# Schematic.net
KiCad netlist of a schematic drawn in Altium Designer
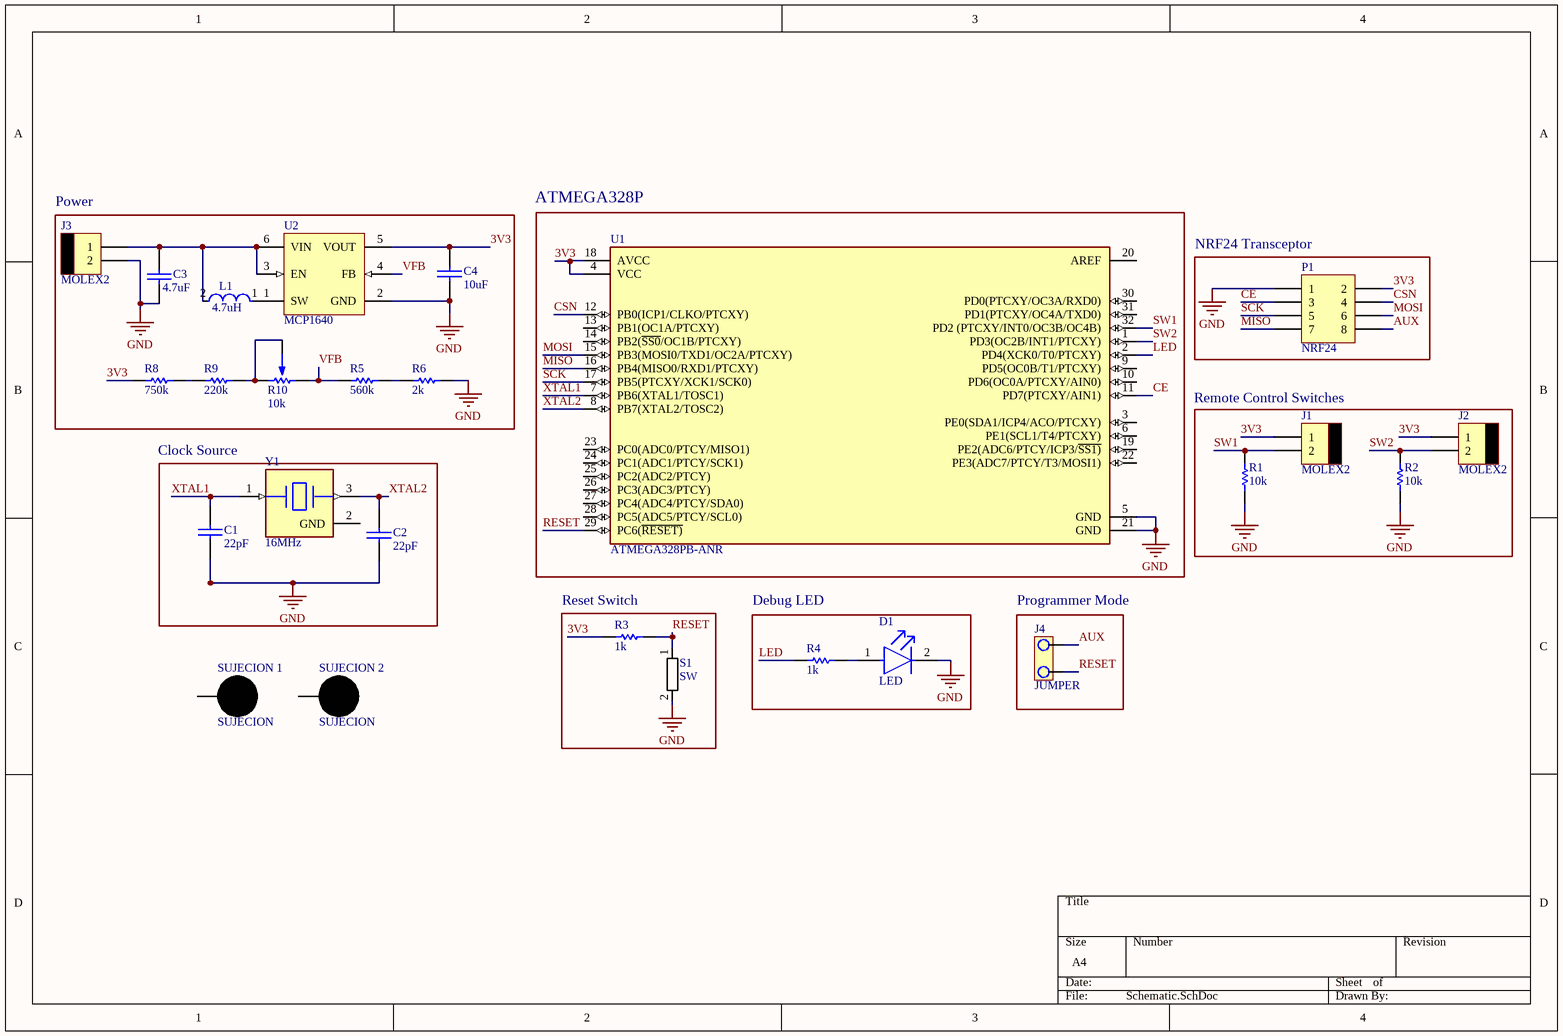
[diagram p0: Schematic.SchDoc]

(export (version "E")
  (design (tool "Eeschema 10.0.6"))
  (components
    (comp (ref "C1") (value "22pF") (footprint "0805") (libsource (lib "LIB PIO IX") (part "CAP")))
    (comp (ref "C2") (value "22pF") (footprint "0805") (libsource (lib "LIB PIO IX") (part "CAP")))
    (comp (ref "C3") (value "4.7uF") (footprint "0805") (libsource (lib "LIB PIO IX") (part "CAP")))
    (comp (ref "C4") (value "10uF") (footprint "0805") (libsource (lib "LIB PIO IX") (part "CAP")))
    (comp (ref "D1")
      (value "LED")
      (footprint "FP-AP1608SGC-MFG")
      (description "Standard LEDs - SMD GREEN WATER CLEAR")
      (libsource (lib "Altium Content Vault") (part "ab1c01a81903e929fc6c44469aada92"))
    )
    (comp (ref "J1") (value "MOLEX2") (footprint "MOLEX2") (libsource (lib "LIB PIO IX") (part "MOLEX2")))
    (comp (ref "J2") (value "MOLEX2") (footprint "MOLEX2") (libsource (lib "LIB PIO IX") (part "MOLEX2")))
    (comp (ref "J3") (value "MOLEX2") (footprint "MOLEX2") (libsource (lib "") (part "MOLEX2_1")))
    (comp (ref "J4") (value "JUMPER") (footprint "JUMPER2") (libsource (lib "LIB PIO IX") (part "JUMPER")))
    (comp (ref "L1")
      (value "4.7uH")
      (footprint "FP-CB2518-IPC_B")
      (description "SMD Inductors 4.7uH ±20% 1.2A 0.13Ω 1007")
      (fields (field (name "TOLERANCE") "20%"))
      (libsource (lib "Altium Content Vault") (part "725321dda6339637d4d059423bc1c3c"))
    )
    (comp (ref "P1")
      (value "NRF24")
      (footprint "HDR2X4")
      (description "Header, 4-Pin, Dual row")
      (fields (field (name "PUBLISHER") "Altium Limited"))
      (libsource (lib "Miscellaneous Connectors") (part "Header 4X2"))
    )
    (comp (ref "R1") (value "10k") (footprint "0805") (libsource (lib "LIB PIO IX") (part "RES")))
    (comp (ref "R2") (value "10k") (footprint "0805") (libsource (lib "LIB PIO IX") (part "RES")))
    (comp (ref "R3") (value "1k") (footprint "0805") (libsource (lib "LIB PIO IX") (part "RES")))
    (comp (ref "R4") (value "1k") (footprint "0805") (libsource (lib "LIB PIO IX") (part "RES")))
    (comp (ref "R5") (value "560k") (footprint "0805") (libsource (lib "LIB PIO IX") (part "RES")))
    (comp (ref "R6") (value "2k") (footprint "0805") (libsource (lib "LIB PIO IX") (part "RES")))
    (comp (ref "R8") (value "750k") (footprint "0805") (libsource (lib "LIB PIO IX") (part "RES")))
    (comp (ref "R9") (value "220k") (footprint "0805") (libsource (lib "LIB PIO IX") (part "RES")))
    (comp (ref "R10") (value "10k") (footprint "PRESET V") (libsource (lib "LIB PIO IX") (part "PRESET")))
    (comp (ref "S1")
      (value "SW")
      (footprint "PCBComponent_1")
      (description "Nano Reset SMD Switch")
      (libsource (lib "SMD_SW") (part "Nano RST SW"))
    )
    (comp (ref "SUJECION 1")
      (value "SUJECION")
      (footprint "SUJECION (5.00MM - 3.50MM)")
      (libsource (lib "LIB2013") (part "SUJECION"))
    )
    (comp (ref "SUJECION 2")
      (value "SUJECION")
      (footprint "SUJECION (5.00MM - 3.50MM)")
      (libsource (lib "LIB2013") (part "SUJECION"))
    )
    (comp (ref "U1")
      (value "ATMEGA328PB-ANR")
      (footprint "FP-C04-074-MFG")
      (description "IC MCU 8BIT 32KB FLASH 32TQFP")
      (libsource (lib "Altium Content Vault") (part "ea72676ab472b9c3d110a3743980b8d"))
    )
    (comp (ref "U2")
      (value "MCP1640")
      (footprint "MCHP-SOT-23-CHY6_M")
      (fields (field (name "MANUFACTURER") "Microchip") (field (name "PARTNUMBER") "MCP1640CT-I/CHY"))
      (libsource (lib "Altium Content Vault") (part "MCHP-MCP16XX-SOT-23-6"))
    )
    (comp (ref "Y1")
      (value "16MHz")
      (footprint "FP-CSTNE16M0V530000R0-MFG")
      (description "CERAMIC RES 16.0000MHZ 15PF SMD")
      (fields
        (field (name "TOLERANCE") "0.5%")
        (field (name "MANUFACTURER PART NUMBER") "CSTNE16M0V530000R0")
      )
      (libsource (lib "Altium Content Vault") (part "f88508b02107a2c8e6f46217c19d2b8"))
    )
  )
  (nets
    (net (code "1") (name "/3V3") (class "Default")
      (node (ref "C4") (pin "1") (pinfunction "1_1") (pintype "passive"))
      (node (ref "J1") (pin "1") (pinfunction "1_1") (pintype "passive"))
      (node (ref "J2") (pin "1") (pinfunction "1_1") (pintype "passive"))
      (node (ref "P1") (pin "2") (pinfunction "2_2") (pintype "passive"))
      (node (ref "R3") (pin "1") (pinfunction "1_1") (pintype "passive"))
      (node (ref "R8") (pin "1") (pinfunction "1_1") (pintype "passive"))
      (node (ref "U1") (pin "18") (pinfunction "AVCC_18") (pintype "power_in"))
      (node (ref "U1") (pin "4") (pinfunction "VCC_4") (pintype "power_in"))
      (node (ref "U2") (pin "5") (pinfunction "VOUT_5") (pintype "power_in"))
    )
    (net (code "2") (name "/AUX") (class "Default")
      (node (ref "J4") (pin "1") (pinfunction "1_1") (pintype "passive"))
      (node (ref "P1") (pin "8") (pinfunction "8_8") (pintype "passive"))
    )
    (net (code "3") (name "/CE") (class "Default")
      (node (ref "P1") (pin "3") (pinfunction "3_3") (pintype "passive"))
      (node (ref "U1") (pin "11") (pinfunction "PD7(PTCXY/AIN1)_11") (pintype "bidirectional"))
    )
    (net (code "4") (name "/CSN") (class "Default")
      (node (ref "P1") (pin "4") (pinfunction "4_4") (pintype "passive"))
      (node (ref "U1") (pin "12") (pinfunction "PB0(ICP1/CLKO/PTCXY)_12") (pintype "bidirectional"))
    )
    (net (code "5") (name "/LED") (class "Default")
      (node (ref "R4") (pin "1") (pinfunction "1_1") (pintype "passive"))
      (node (ref "U1") (pin "2") (pinfunction "PD4(XCK0/T0/PTCXY)_2") (pintype "bidirectional"))
    )
    (net (code "6") (name "/MISO") (class "Default")
      (node (ref "P1") (pin "7") (pinfunction "7_7") (pintype "passive"))
      (node (ref "U1") (pin "16") (pinfunction "PB4(MISO0/RXD1/PTCXY)_16") (pintype "bidirectional"))
    )
    (net (code "7") (name "/MOSI") (class "Default")
      (node (ref "P1") (pin "6") (pinfunction "6_6") (pintype "passive"))
      (node (ref "U1") (pin "15") (pinfunction "PB3(MOSI0/TXD1/OC2A/PTCXY)_15") (pintype "bidirectional"))
    )
    (net (code "8") (name "/RESET") (class "Default")
      (node (ref "J4") (pin "2") (pinfunction "2_2") (pintype "passive"))
      (node (ref "R3") (pin "2") (pinfunction "2_2") (pintype "passive"))
      (node (ref "S1") (pin "1") (pintype "passive"))
      (node (ref "U1") (pin "29") (pinfunction "PC6(~{RESET)}_29") (pintype "bidirectional"))
    )
    (net (code "9") (name "/SCK") (class "Default")
      (node (ref "P1") (pin "5") (pinfunction "5_5") (pintype "passive"))
      (node (ref "U1") (pin "17") (pinfunction "PB5(PTCXY/XCK1/SCK0)_17") (pintype "bidirectional"))
    )
    (net (code "10") (name "/SW1") (class "Default")
      (node (ref "J1") (pin "2") (pinfunction "2_2") (pintype "passive"))
      (node (ref "R1") (pin "2") (pinfunction "2_2") (pintype "passive"))
      (node (ref "U1") (pin "32") (pinfunction "PD2_(PTCXY/INT0/OC3B/OC4B)_32") (pintype "bidirectional"))
    )
    (net (code "11") (name "/SW2") (class "Default")
      (node (ref "J2") (pin "2") (pinfunction "2_2") (pintype "passive"))
      (node (ref "R2") (pin "2") (pinfunction "2_2") (pintype "passive"))
      (node (ref "U1") (pin "1") (pinfunction "PD3(OC2B/INT1/PTCXY)_1") (pintype "bidirectional"))
    )
    (net (code "12") (name "/VFB") (class "Default")
      (node (ref "R10") (pin "3") (pinfunction "3_3") (pintype "passive"))
      (node (ref "R5") (pin "1") (pinfunction "1_1") (pintype "passive"))
      (node (ref "U2") (pin "4") (pinfunction "FB_4") (pintype "input"))
    )
    (net (code "13") (name "/XTAL1") (class "Default")
      (node (ref "C1") (pin "1") (pinfunction "1_1") (pintype "passive"))
      (node (ref "U1") (pin "7") (pinfunction "PB6(XTAL1/TOSC1)_7") (pintype "bidirectional"))
      (node (ref "Y1") (pin "1") (pinfunction "Input_1") (pintype "input"))
    )
    (net (code "14") (name "/XTAL2") (class "Default")
      (node (ref "C2") (pin "1") (pinfunction "1_1") (pintype "passive"))
      (node (ref "U1") (pin "8") (pinfunction "PB7(XTAL2/TOSC2)_8") (pintype "bidirectional"))
      (node (ref "Y1") (pin "3") (pinfunction "Output_3") (pintype "output"))
    )
    (net (code "15") (name "GND") (class "Default")
      (node (ref "C1") (pin "2") (pinfunction "2_2") (pintype "passive"))
      (node (ref "C2") (pin "2") (pinfunction "2_2") (pintype "passive"))
      (node (ref "C3") (pin "2") (pinfunction "2_2") (pintype "passive"))
      (node (ref "C4") (pin "2") (pinfunction "2_2") (pintype "passive"))
      (node (ref "D1") (pin "2") (pinfunction "C_2") (pintype "passive"))
      (node (ref "J3") (pin "2") (pinfunction "2_2") (pintype "passive"))
      (node (ref "P1") (pin "1") (pinfunction "1_1") (pintype "passive"))
      (node (ref "R1") (pin "1") (pinfunction "1_1") (pintype "passive"))
      (node (ref "R2") (pin "1") (pinfunction "1_1") (pintype "passive"))
      (node (ref "R6") (pin "2") (pinfunction "2_2") (pintype "passive"))
      (node (ref "S1") (pin "2") (pintype "passive"))
      (node (ref "U1") (pin "21") (pinfunction "GND_21") (pintype "power_in"))
      (node (ref "U1") (pin "5") (pinfunction "GND_5") (pintype "power_in"))
      (node (ref "U2") (pin "2") (pinfunction "GND_2") (pintype "power_in"))
    )
    (net (code "16") (name "Net-(D1-A)") (class "Default")
      (node (ref "D1") (pin "1") (pinfunction "A_1") (pintype "passive"))
      (node (ref "R4") (pin "2") (pinfunction "2_2") (pintype "passive"))
    )
    (net (code "17") (name "Net-(R5-Pad2)") (class "Default")
      (node (ref "R5") (pin "2") (pinfunction "2_2") (pintype "passive"))
      (node (ref "R6") (pin "1") (pinfunction "1_1") (pintype "passive"))
    )
    (net (code "18") (name "Net-(R8-Pad2)") (class "Default")
      (node (ref "R8") (pin "2") (pinfunction "2_2") (pintype "passive"))
      (node (ref "R9") (pin "1") (pinfunction "1_1") (pintype "passive"))
    )
    (net (code "19") (name "Net-(R10-Pad1)") (class "Default")
      (node (ref "R10") (pin "1") (pinfunction "1_1") (pintype "passive"))
      (node (ref "R10") (pin "2") (pinfunction "2_2") (pintype "passive"))
      (node (ref "R9") (pin "2") (pinfunction "2_2") (pintype "passive"))
    )
    (net (code "20") (name "Net-(U2-EN)") (class "Default")
      (node (ref "C3") (pin "1") (pinfunction "1_1") (pintype "passive"))
      (node (ref "J3") (pin "1") (pinfunction "1_1") (pintype "passive"))
      (node (ref "L1") (pin "2") (pinfunction "2_2") (pintype "passive"))
      (node (ref "U2") (pin "3") (pinfunction "EN_3") (pintype "input"))
      (node (ref "U2") (pin "6") (pinfunction "VIN_6") (pintype "power_in"))
    )
    (net (code "21") (name "Net-(U2-SW)") (class "Default")
      (node (ref "L1") (pin "1") (pinfunction "1_1") (pintype "passive"))
      (node (ref "U2") (pin "1") (pinfunction "SW_1") (pintype "power_in"))
    )
    (net (code "22") (name "unconnected-(SUJECION 1-Pad1)") (class "Default")
      (node (ref "SUJECION 1") (pin "1") (pinfunction "1_1") (pintype "passive"))
    )
    (net (code "23") (name "unconnected-(SUJECION 2-Pad1)") (class "Default")
      (node (ref "SUJECION 2") (pin "1") (pinfunction "1_1") (pintype "passive"))
    )
    (net (code "24") (name "unconnected-(U1-AREF-Pad20)") (class "Default")
      (node (ref "U1") (pin "20") (pinfunction "AREF_20") (pintype "passive"))
    )
    (net (code "25") (name "unconnected-(U1-PB1(OC1A{slash}PTCXY)-Pad13)") (class "Default")
      (node (ref "U1") (pin "13") (pinfunction "PB1(OC1A/PTCXY)_13") (pintype "bidirectional"))
    )
    (net (code "26") (name "unconnected-(U1-PB2(~{SS0}{slash}OC1B{slash}PTCXY)-Pad14)") (class "Default")
      (node (ref "U1") (pin "14") (pinfunction "PB2(~{SS0}/OC1B/PTCXY)_14") (pintype "bidirectional"))
    )
    (net (code "27") (name "unconnected-(U1-PC0(ADC0{slash}PTCY{slash}MISO1)-Pad23)") (class "Default")
      (node (ref "U1") (pin "23") (pinfunction "PC0(ADC0/PTCY/MISO1)_23") (pintype "bidirectional"))
    )
    (net (code "28") (name "unconnected-(U1-PC1(ADC1{slash}PTCY{slash}SCK1)-Pad24)") (class "Default")
      (node (ref "U1") (pin "24") (pinfunction "PC1(ADC1/PTCY/SCK1)_24") (pintype "bidirectional"))
    )
    (net (code "29") (name "unconnected-(U1-PC2(ADC2{slash}PTCY)-Pad25)") (class "Default")
      (node (ref "U1") (pin "25") (pinfunction "PC2(ADC2/PTCY)_25") (pintype "bidirectional"))
    )
    (net (code "30") (name "unconnected-(U1-PC3(ADC3{slash}PTCY)-Pad26)") (class "Default")
      (node (ref "U1") (pin "26") (pinfunction "PC3(ADC3/PTCY)_26") (pintype "bidirectional"))
    )
    (net (code "31") (name "unconnected-(U1-PC4(ADC4{slash}PTCY{slash}SDA0)-Pad27)") (class "Default")
      (node (ref "U1") (pin "27") (pinfunction "PC4(ADC4/PTCY/SDA0)_27") (pintype "bidirectional"))
    )
    (net (code "32") (name "unconnected-(U1-PC5(ADC5{slash}PTCY{slash}SCL0)-Pad28)") (class "Default")
      (node (ref "U1") (pin "28") (pinfunction "PC5(ADC5/PTCY/SCL0)_28") (pintype "bidirectional"))
    )
    (net (code "33") (name "unconnected-(U1-PD0(PTCXY{slash}OC3A{slash}RXD0)-Pad30)") (class "Default")
      (node (ref "U1") (pin "30") (pinfunction "PD0(PTCXY/OC3A/RXD0)_30") (pintype "bidirectional"))
    )
    (net (code "34") (name "unconnected-(U1-PD1(PTCXY{slash}OC4A{slash}TXD0)-Pad31)") (class "Default")
      (node (ref "U1") (pin "31") (pinfunction "PD1(PTCXY/OC4A/TXD0)_31") (pintype "bidirectional"))
    )
    (net (code "35") (name "unconnected-(U1-PD5(OC0B{slash}T1{slash}PTCXY)-Pad9)") (class "Default")
      (node (ref "U1") (pin "9") (pinfunction "PD5(OC0B/T1/PTCXY)_9") (pintype "bidirectional"))
    )
    (net (code "36") (name "unconnected-(U1-PD6(OC0A{slash}PTCXY{slash}AIN0)-Pad10)") (class "Default")
      (node (ref "U1") (pin "10") (pinfunction "PD6(OC0A/PTCXY/AIN0)_10") (pintype "bidirectional"))
    )
    (net (code "37") (name "unconnected-(U1-PE0(SDA1{slash}ICP4{slash}ACO{slash}PTCXY)-Pad3)") (class "Default")
      (node (ref "U1") (pin "3") (pinfunction "PE0(SDA1/ICP4/ACO/PTCXY)_3") (pintype "bidirectional"))
    )
    (net (code "38") (name "unconnected-(U1-PE1(SCL1{slash}T4{slash}PTCXY)-Pad6)") (class "Default")
      (node (ref "U1") (pin "6") (pinfunction "PE1(SCL1/T4/PTCXY)_6") (pintype "bidirectional"))
    )
    (net (code "39") (name "unconnected-(U1-PE2(ADC6{slash}PTCY{slash}ICP3{slash}~{SS1)}-Pad19)") (class "Default")
      (node (ref "U1") (pin "19") (pinfunction "PE2(ADC6/PTCY/ICP3/~{SS1)}_19") (pintype "bidirectional"))
    )
    (net (code "40") (name "unconnected-(U1-PE3(ADC7{slash}PTCY{slash}T3{slash}MOSI1)-Pad22)") (class "Default")
      (node (ref "U1") (pin "22") (pinfunction "PE3(ADC7/PTCY/T3/MOSI1)_22") (pintype "bidirectional"))
    )
    (net (code "41") (name "unconnected-(Y1-GND-Pad2)") (class "Default")
      (node (ref "Y1") (pin "2") (pinfunction "GND_2") (pintype "power_in"))
    )
  )
)
